# WiFiGeiger.net
KiCad netlist of a schematic drawn in EAGLE
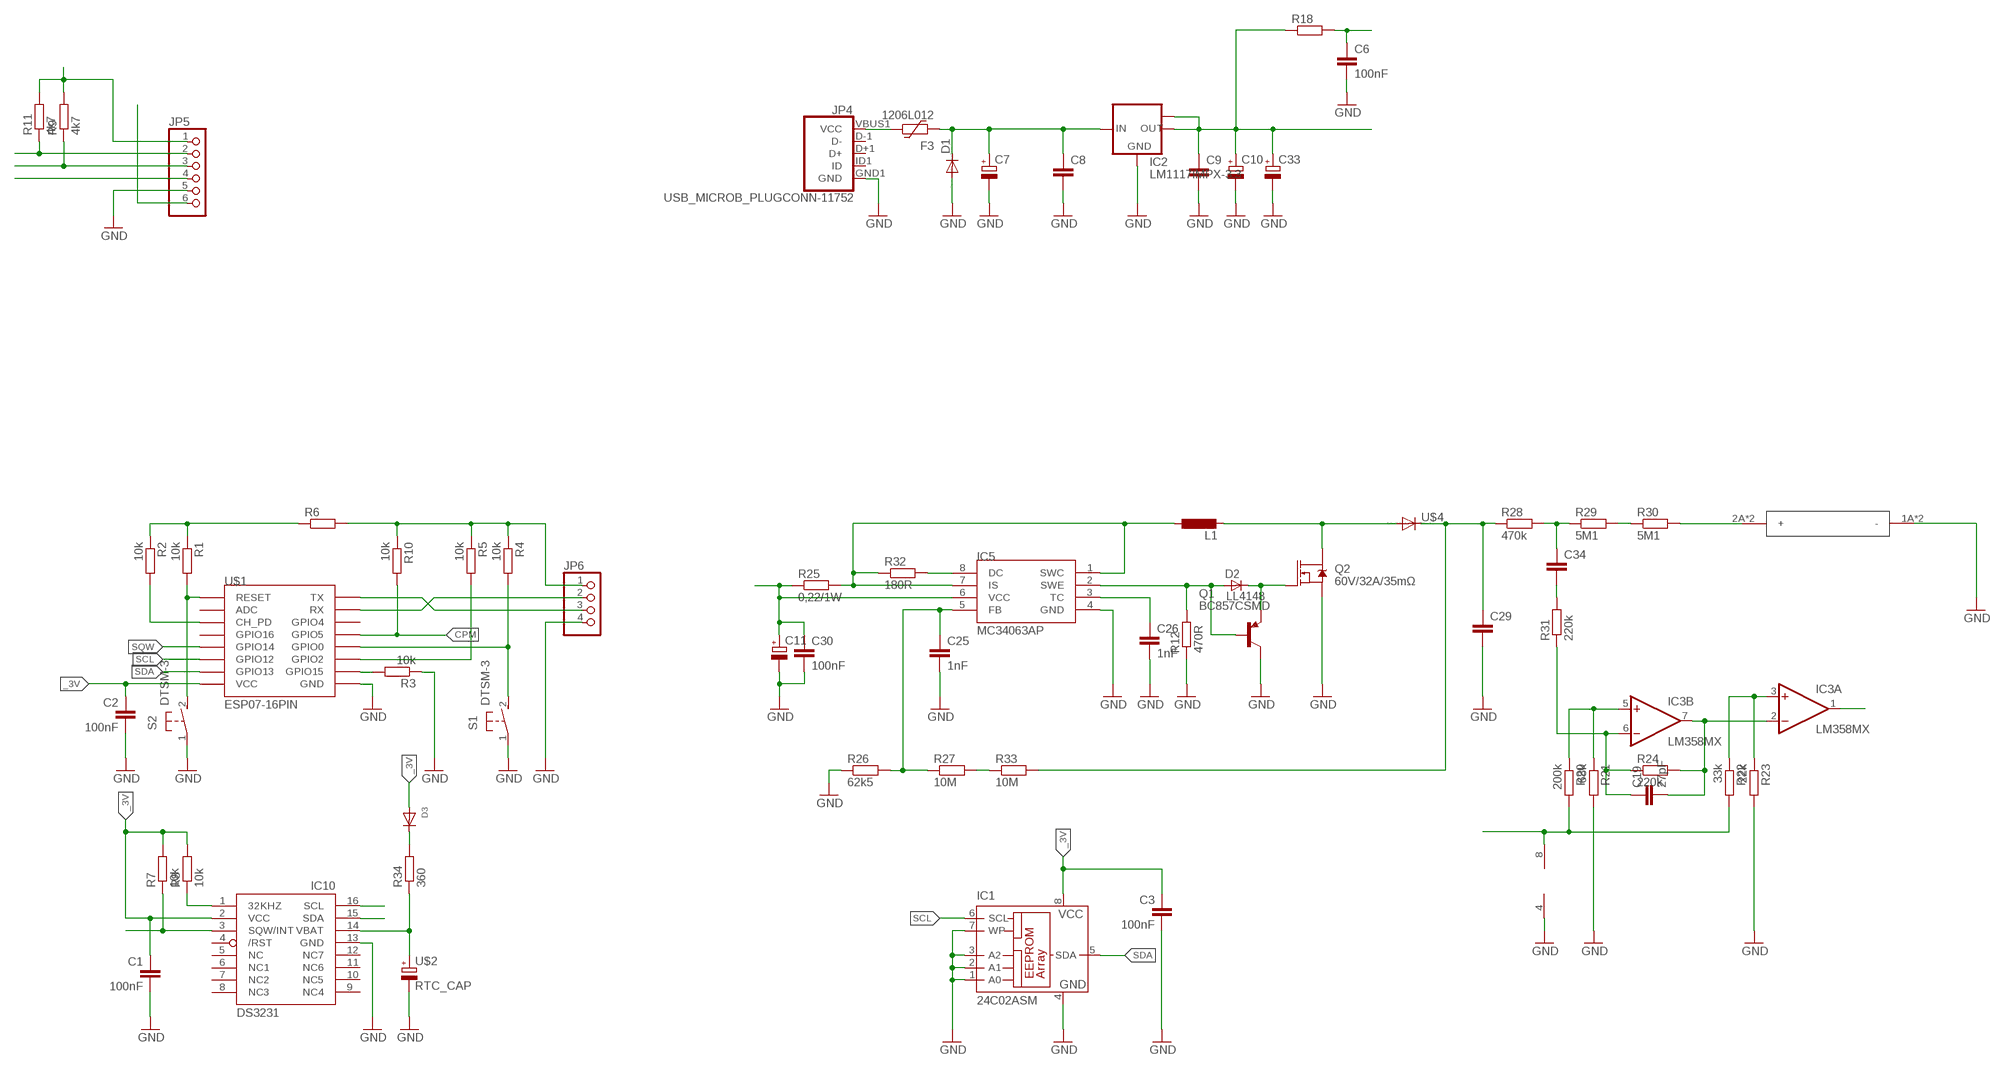
[diagram p0: schematic, sheet 1]

(export (version "E")
  (design (tool "Eeschema 10.0.6"))
  (components
    (comp (ref "C1")
      (value "100nF")
      (footprint "eagle-import:C0603")
      (libsource (lib "eagle-import") (part "C-EUC0603"))
    )
    (comp (ref "C2")
      (value "100nF")
      (footprint "eagle-import:C0603")
      (libsource (lib "eagle-import") (part "C-EUC0603"))
    )
    (comp (ref "C3")
      (value "100nF")
      (footprint "eagle-import:C0603")
      (libsource (lib "eagle-import") (part "C-EUC0603"))
    )
    (comp (ref "C6")
      (value "100nF")
      (footprint "eagle-import:C0603")
      (libsource (lib "eagle-import") (part "C-EUC0603"))
    )
    (comp (ref "C7")
      (value "CPOL-EUSMCC")
      (footprint "eagle-import:SMC_C")
      (libsource (lib "eagle-import") (part "CPOL-EUSMCC"))
    )
    (comp (ref "C8")
      (value "C-EUC1206")
      (footprint "eagle-import:C1206")
      (libsource (lib "eagle-import") (part "C-EUC1206"))
    )
    (comp (ref "C9")
      (value "C-EUC1206")
      (footprint "eagle-import:C1206")
      (libsource (lib "eagle-import") (part "C-EUC1206"))
    )
    (comp (ref "C10")
      (value "CPOL-EUSMCC")
      (footprint "eagle-import:SMC_C")
      (libsource (lib "eagle-import") (part "CPOL-EUSMCC"))
    )
    (comp (ref "C11")
      (value "CPOL-EUSMCE")
      (footprint "eagle-import:SMC_E")
      (libsource (lib "eagle-import") (part "CPOL-EUSMCE"))
    )
    (comp (ref "C19")
      (value "27pF")
      (footprint "eagle-import:C0603")
      (libsource (lib "eagle-import") (part "C-EUC0603"))
    )
    (comp (ref "C25")
      (value "1nF")
      (footprint "eagle-import:C0603")
      (libsource (lib "eagle-import") (part "C-EUC0603"))
    )
    (comp (ref "C26")
      (value "1nF")
      (footprint "eagle-import:C0603")
      (libsource (lib "eagle-import") (part "C-EUC0603"))
    )
    (comp (ref "C29")
      (value "C-EU225-113X268")
      (footprint "eagle-import:C225-113X268")
      (libsource (lib "eagle-import") (part "C-EU225-113X268"))
    )
    (comp (ref "C30")
      (value "100nF")
      (footprint "eagle-import:C0603")
      (libsource (lib "eagle-import") (part "C-EUC0603"))
    )
    (comp (ref "C33")
      (value "CPOL-EUSMCB")
      (footprint "eagle-import:SMC_B")
      (libsource (lib "eagle-import") (part "CPOL-EUSMCB"))
    )
    (comp (ref "C34")
      (value "C-EU050-024X044")
      (footprint "eagle-import:C050-024X044")
      (libsource (lib "eagle-import") (part "C-EU050-024X044"))
    )
    (comp (ref "D1")
      (value "DIODE-SMB")
      (footprint "eagle-import:SMB")
      (libsource (lib "eagle-import") (part "DIODE-SMB"))
    )
    (comp (ref "D2")
      (value "LL4148")
      (footprint "eagle-import:SOD80_DO213AA_MINIMELF")
      (libsource (lib "eagle-import") (part "LL4148"))
    )
    (comp (ref "D3")
      (value "DIODESMA")
      (footprint "eagle-import:SMADIODE")
      (libsource (lib "eagle-import") (part "DIODESMA"))
    )
    (comp (ref "F3")
      (value "1206L012")
      (footprint "eagle-import:1206L")
      (fields (field (name "MF") "Littelfuse"))
      (libsource (lib "eagle-import") (part "?1206L012"))
    )
    (comp (ref "IC1")
      (value "24C02ASM")
      (footprint "eagle-import:SO-08M")
      (fields (field (name "MF") "MICROCHIP") (field (name "MPN") "24C02C/SN"))
      (libsource (lib "eagle-import") (part "24SMC02A"))
    )
    (comp (ref "IC2")
      (value "LM1117IMPX-3.3")
      (footprint "eagle-import:SOT223")
      (libsource (lib "eagle-import") (part "LM1117IMPX-3.3"))
    )
    (comp (ref "IC3")
      (value "LM358MX")
      (footprint "eagle-import:SO08")
      (libsource (lib "eagle-import") (part "LM358MX"))
    )
    (comp (ref "IC5")
      (value "MC34063AP")
      (footprint "eagle-import:DIL08")
      (libsource (lib "eagle-import") (part "MC34063AP"))
    )
    (comp (ref "IC10")
      (value "DS3231/SO")
      (footprint "eagle-import:SO16W")
      (libsource (lib "eagle-import") (part "DS3231/SO"))
    )
    (comp (ref "JP4")
      (value "USB_MICROB_PLUGCONN-11752")
      (footprint "eagle-import:USB-B-MICRO-SMD_V03")
      (libsource (lib "eagle-import") (part "USB_MICROB_PLUGCONN-11752"))
    )
    (comp (ref "JP5")
      (value "PINHD-1X6")
      (footprint "eagle-import:1X06")
      (libsource (lib "eagle-import") (part "PINHD-1X6"))
    )
    (comp (ref "JP6")
      (value "PINHD-1X4")
      (footprint "eagle-import:1X04")
      (libsource (lib "eagle-import") (part "PINHD-1X4"))
    )
    (comp (ref "L1")
      (value "L-EU6000-XXX-RC")
      (footprint "eagle-import:6000-XXXX-RC")
      (libsource (lib "eagle-import") (part "L-EU6000-XXX-RC"))
    )
    (comp (ref "Q1")
      (value "BC857CSMD")
      (footprint "eagle-import:SOT23-BEC")
      (libsource (lib "eagle-import") (part "BC857SMDC"))
    )
    (comp (ref "Q2")
      (value "60V/32A/35mΩ")
      (footprint "eagle-import:TO220V")
      (libsource (lib "eagle-import") (part "MOSFET-NCH-FQP30N06L"))
    )
    (comp (ref "R1")
      (value "10k")
      (footprint "eagle-import:R0603")
      (libsource (lib "eagle-import") (part "R-EU_R0603"))
    )
    (comp (ref "R2")
      (value "10k")
      (footprint "eagle-import:R0603")
      (libsource (lib "eagle-import") (part "R-EU_R0603"))
    )
    (comp (ref "R3")
      (value "10k")
      (footprint "eagle-import:R0603")
      (libsource (lib "eagle-import") (part "R-EU_R0603"))
    )
    (comp (ref "R4")
      (value "10k")
      (footprint "eagle-import:R0603")
      (libsource (lib "eagle-import") (part "R-EU_R0603"))
    )
    (comp (ref "R5")
      (value "10k")
      (footprint "eagle-import:R0603")
      (libsource (lib "eagle-import") (part "R-EU_R0603"))
    )
    (comp (ref "R6")
      (value "R-EU_R2010")
      (footprint "eagle-import:R2010")
      (libsource (lib "eagle-import") (part "R-EU_R2010"))
    )
    (comp (ref "R7")
      (value "10k")
      (footprint "eagle-import:R0603")
      (libsource (lib "eagle-import") (part "R-EU_R0603"))
    )
    (comp (ref "R8")
      (value "10k")
      (footprint "eagle-import:R0603")
      (libsource (lib "eagle-import") (part "R-EU_R0603"))
    )
    (comp (ref "R9")
      (value "4k7")
      (footprint "eagle-import:R0603")
      (libsource (lib "eagle-import") (part "R-EU_R0603"))
    )
    (comp (ref "R10")
      (value "10k")
      (footprint "eagle-import:R0603")
      (libsource (lib "eagle-import") (part "R-EU_R0603"))
    )
    (comp (ref "R11")
      (value "4k7")
      (footprint "eagle-import:R0603")
      (libsource (lib "eagle-import") (part "R-EU_R0603"))
    )
    (comp (ref "R12")
      (value "470R")
      (footprint "eagle-import:R1206")
      (libsource (lib "eagle-import") (part "R-EU_R1206"))
    )
    (comp (ref "R18")
      (value "R-EU_R1206")
      (footprint "eagle-import:R1206")
      (libsource (lib "eagle-import") (part "R-EU_R1206"))
    )
    (comp (ref "R20")
      (value "200k")
      (footprint "eagle-import:R0603")
      (libsource (lib "eagle-import") (part "R-EU_R0603"))
    )
    (comp (ref "R21")
      (value "68k")
      (footprint "eagle-import:R0603")
      (libsource (lib "eagle-import") (part "R-EU_R0603"))
    )
    (comp (ref "R22")
      (value "33k")
      (footprint "eagle-import:R1206")
      (libsource (lib "eagle-import") (part "R-EU_R1206"))
    )
    (comp (ref "R23")
      (value "22k")
      (footprint "eagle-import:R0603")
      (libsource (lib "eagle-import") (part "R-EU_R0603"))
    )
    (comp (ref "R24")
      (value "220k")
      (footprint "eagle-import:R0603")
      (libsource (lib "eagle-import") (part "R-EU_R0603"))
    )
    (comp (ref "R25")
      (value "0,22/1W")
      (footprint "eagle-import:R2010")
      (libsource (lib "eagle-import") (part "R-EU_R2010"))
    )
    (comp (ref "R26")
      (value "62k5")
      (footprint "eagle-import:R1206")
      (libsource (lib "eagle-import") (part "R-EU_R1206"))
    )
    (comp (ref "R27")
      (value "10M")
      (footprint "eagle-import:R2512")
      (libsource (lib "eagle-import") (part "R-EU_R2512"))
    )
    (comp (ref "R28")
      (value "470k")
      (footprint "eagle-import:R2512")
      (libsource (lib "eagle-import") (part "R-EU_R2512"))
    )
    (comp (ref "R29")
      (value "5M1")
      (footprint "eagle-import:R2512")
      (libsource (lib "eagle-import") (part "R-EU_R2512"))
    )
    (comp (ref "R30")
      (value "5M1")
      (footprint "eagle-import:R2512")
      (libsource (lib "eagle-import") (part "R-EU_R2512"))
    )
    (comp (ref "R31")
      (value "220k")
      (footprint "eagle-import:R0805")
      (libsource (lib "eagle-import") (part "R-EU_R0805"))
    )
    (comp (ref "R32")
      (value "180R")
      (footprint "eagle-import:R0805")
      (libsource (lib "eagle-import") (part "R-EU_R0805"))
    )
    (comp (ref "R33")
      (value "10M")
      (footprint "eagle-import:R2512")
      (libsource (lib "eagle-import") (part "R-EU_R2512"))
    )
    (comp (ref "R34")
      (value "360")
      (footprint "eagle-import:R0603")
      (libsource (lib "eagle-import") (part "R-EU_R0603"))
    )
    (comp (ref "S1")
      (value "DTSM-3")
      (footprint "eagle-import:DTSM-3")
      (libsource (lib "eagle-import") (part "DTSM-3"))
    )
    (comp (ref "S2")
      (value "DTSM-3")
      (footprint "eagle-import:DTSM-3")
      (libsource (lib "eagle-import") (part "DTSM-3"))
    )
    (comp (ref "U$1")
      (value "ESP07-16PIN")
      (footprint "eagle-import:ESP07-16PIN")
      (libsource (lib "eagle-import") (part "ESP07-16PIN"))
    )
    (comp (ref "U$2")
      (value "RTC_CAP")
      (footprint "eagle-import:RTC_CAP")
      (libsource (lib "eagle-import") (part "RTC_CAP"))
    )
    (comp (ref "U$4")
      (value "DIODE-MELF-MLL41")
      (footprint "eagle-import:MELF-MLL41")
      (libsource (lib "eagle-import") (part "DIODE-MELF-MLL41"))
    )
    (comp (ref "U$5")
      (value "STS5")
      (footprint "eagle-import:GEIGERTUBE")
      (libsource (lib "eagle-import") (part "STS5"))
    )
  )
  (nets
    (net (code "1") (name "/A_3V") (class "Default")
      (node (ref "C6") (pin "1") (pinfunction "1_1") (pintype "passive"))
      (node (ref "IC3") (pin "8") (pinfunction "V+_8") (pintype "power_in"))
      (node (ref "R18") (pin "2") (pinfunction "2_2") (pintype "passive"))
      (node (ref "R20") (pin "2") (pinfunction "2_2") (pintype "passive"))
      (node (ref "R22") (pin "2") (pinfunction "2_2") (pintype "passive"))
    )
    (net (code "2") (name "/VBUS") (class "Default")
      (node (ref "C11") (pin "+") (pinfunction "+_+") (pintype "passive"))
      (node (ref "C30") (pin "1") (pinfunction "1_1") (pintype "passive"))
      (node (ref "C7") (pin "+") (pinfunction "+_+") (pintype "passive"))
      (node (ref "C8") (pin "1") (pinfunction "1_1") (pintype "passive"))
      (node (ref "D1") (pin "C") (pinfunction "C_C") (pintype "passive"))
      (node (ref "F3") (pin "2") (pinfunction "2_2") (pintype "passive"))
      (node (ref "IC2") (pin "3") (pinfunction "IN_3") (pintype "input"))
      (node (ref "IC5") (pin "6") (pinfunction "VCC_6") (pintype "passive"))
      (node (ref "JP5") (pin "6") (pinfunction "6_6") (pintype "passive"))
      (node (ref "R25") (pin "1") (pinfunction "1_1") (pintype "passive"))
    )
    (net (code "3") (name "CPM") (class "Default")
      (node (ref "IC3") (pin "1") (pinfunction "OUT_1") (pintype "output"))
      (node (ref "R10") (pin "2") (pinfunction "2_2") (pintype "passive"))
      (node (ref "U$1") (pin "GPIO5") (pinfunction "GPIO5_GPIO5") (pintype "bidirectional"))
    )
    (net (code "4") (name "GND") (class "Default")
      (node (ref "C1") (pin "2") (pinfunction "2_2") (pintype "passive"))
      (node (ref "C10") (pin "-") (pinfunction "-_-") (pintype "passive"))
      (node (ref "C11") (pin "-") (pinfunction "-_-") (pintype "passive"))
      (node (ref "C2") (pin "2") (pinfunction "2_2") (pintype "passive"))
      (node (ref "C25") (pin "2") (pinfunction "2_2") (pintype "passive"))
      (node (ref "C26") (pin "2") (pinfunction "2_2") (pintype "passive"))
      (node (ref "C29") (pin "2") (pinfunction "2_2") (pintype "passive"))
      (node (ref "C3") (pin "2") (pinfunction "2_2") (pintype "passive"))
      (node (ref "C30") (pin "2") (pinfunction "2_2") (pintype "passive"))
      (node (ref "C33") (pin "-") (pinfunction "-_-") (pintype "passive"))
      (node (ref "C6") (pin "2") (pinfunction "2_2") (pintype "passive"))
      (node (ref "C7") (pin "-") (pinfunction "-_-") (pintype "passive"))
      (node (ref "C8") (pin "2") (pinfunction "2_2") (pintype "passive"))
      (node (ref "C9") (pin "2") (pinfunction "2_2") (pintype "passive"))
      (node (ref "D1") (pin "A") (pinfunction "A_A") (pintype "passive"))
      (node (ref "IC1") (pin "1") (pinfunction "A0_1") (pintype "input"))
      (node (ref "IC1") (pin "2") (pinfunction "A1_2") (pintype "input"))
      (node (ref "IC1") (pin "3") (pinfunction "A2_3") (pintype "input"))
      (node (ref "IC1") (pin "4") (pinfunction "GND_4") (pintype "power_in"))
      (node (ref "IC1") (pin "7") (pinfunction "WP_7") (pintype "input"))
      (node (ref "IC10") (pin "13") (pinfunction "GND_13") (pintype "power_in"))
      (node (ref "IC2") (pin "1") (pinfunction "GND_1") (pintype "input"))
      (node (ref "IC3") (pin "4") (pinfunction "V-_4") (pintype "power_in"))
      (node (ref "IC5") (pin "4") (pinfunction "GND_4") (pintype "passive"))
      (node (ref "JP4") (pin "GND1") (pinfunction "GND_GND1") (pintype "bidirectional"))
      (node (ref "JP5") (pin "5") (pinfunction "5_5") (pintype "passive"))
      (node (ref "JP6") (pin "4") (pinfunction "4_4") (pintype "passive"))
      (node (ref "Q1") (pin "C") (pinfunction "C_C") (pintype "passive"))
      (node (ref "Q2") (pin "3") (pinfunction "S_3") (pintype "bidirectional"))
      (node (ref "R12") (pin "1") (pinfunction "1_1") (pintype "passive"))
      (node (ref "R21") (pin "2") (pinfunction "2_2") (pintype "passive"))
      (node (ref "R23") (pin "2") (pinfunction "2_2") (pintype "passive"))
      (node (ref "R26") (pin "1") (pinfunction "1_1") (pintype "passive"))
      (node (ref "R3") (pin "1") (pinfunction "1_1") (pintype "passive"))
      (node (ref "S1") (pin "1") (pinfunction "1_1") (pintype "passive"))
      (node (ref "S2") (pin "1") (pinfunction "1_1") (pintype "passive"))
      (node (ref "U$1") (pin "GND") (pinfunction "GND_GND") (pintype "bidirectional"))
      (node (ref "U$2") (pin "P$2") (pinfunction "-_P$2") (pintype "passive"))
      (node (ref "U$5") (pin "1A") (pinfunction "-_1A") (pintype "bidirectional"))
      (node (ref "U$5") (pin "1B") (pinfunction "-_1B") (pintype "bidirectional"))
    )
    (net (code "5") (name "Net-(C29-Pad1)") (class "Default")
      (node (ref "C29") (pin "1") (pinfunction "1_1") (pintype "passive"))
      (node (ref "R28") (pin "1") (pinfunction "1_1") (pintype "passive"))
      (node (ref "R33") (pin "2") (pinfunction "2_2") (pintype "passive"))
      (node (ref "U$4") (pin "C") (pinfunction "C_C") (pintype "passive"))
    )
    (net (code "6") (name "Net-(C34-Pad1)") (class "Default")
      (node (ref "C34") (pin "1") (pinfunction "1_1") (pintype "passive"))
      (node (ref "R28") (pin "2") (pinfunction "2_2") (pintype "passive"))
      (node (ref "R29") (pin "1") (pinfunction "1_1") (pintype "passive"))
    )
    (net (code "7") (name "Net-(C34-Pad2)") (class "Default")
      (node (ref "C34") (pin "2") (pinfunction "2_2") (pintype "passive"))
      (node (ref "R31") (pin "2") (pinfunction "2_2") (pintype "passive"))
    )
    (net (code "8") (name "Net-(D3-PadC)") (class "Default")
      (node (ref "D3") (pin "C") (pinfunction "C_C") (pintype "passive"))
      (node (ref "R34") (pin "2") (pinfunction "2_2") (pintype "passive"))
    )
    (net (code "9") (name "Net-(IC3A-+IN)") (class "Default")
      (node (ref "IC3") (pin "3") (pinfunction "+IN_3") (pintype "input"))
      (node (ref "R22") (pin "1") (pinfunction "1_1") (pintype "passive"))
      (node (ref "R23") (pin "1") (pinfunction "1_1") (pintype "passive"))
    )
    (net (code "10") (name "Net-(IC3A--IN)") (class "Default")
      (node (ref "C19") (pin "2") (pinfunction "2_2") (pintype "passive"))
      (node (ref "IC3") (pin "2") (pinfunction "-IN_2") (pintype "input"))
      (node (ref "IC3") (pin "7") (pinfunction "OUT_7") (pintype "output"))
      (node (ref "R24") (pin "2") (pinfunction "2_2") (pintype "passive"))
    )
    (net (code "11") (name "Net-(IC3B-+IN)") (class "Default")
      (node (ref "IC3") (pin "5") (pinfunction "+IN_5") (pintype "input"))
      (node (ref "R20") (pin "1") (pinfunction "1_1") (pintype "passive"))
      (node (ref "R21") (pin "1") (pinfunction "1_1") (pintype "passive"))
    )
    (net (code "12") (name "Net-(IC3B--IN)") (class "Default")
      (node (ref "C19") (pin "1") (pinfunction "1_1") (pintype "passive"))
      (node (ref "IC3") (pin "6") (pinfunction "-IN_6") (pintype "input"))
      (node (ref "R24") (pin "1") (pinfunction "1_1") (pintype "passive"))
      (node (ref "R31") (pin "1") (pinfunction "1_1") (pintype "passive"))
    )
    (net (code "13") (name "Net-(IC5-DC)") (class "Default")
      (node (ref "IC5") (pin "8") (pinfunction "DC_8") (pintype "passive"))
      (node (ref "R32") (pin "2") (pinfunction "2_2") (pintype "passive"))
    )
    (net (code "14") (name "Net-(IC5-FB)") (class "Default")
      (node (ref "C25") (pin "1") (pinfunction "1_1") (pintype "passive"))
      (node (ref "IC5") (pin "5") (pinfunction "FB_5") (pintype "passive"))
      (node (ref "R26") (pin "2") (pinfunction "2_2") (pintype "passive"))
      (node (ref "R27") (pin "1") (pinfunction "1_1") (pintype "passive"))
    )
    (net (code "15") (name "Net-(IC5-IS)") (class "Default")
      (node (ref "IC5") (pin "1") (pinfunction "SWC_1") (pintype "passive"))
      (node (ref "IC5") (pin "7") (pinfunction "IS_7") (pintype "passive"))
      (node (ref "L1") (pin "1") (pinfunction "1_1") (pintype "passive"))
      (node (ref "R25") (pin "2") (pinfunction "2_2") (pintype "passive"))
      (node (ref "R32") (pin "1") (pinfunction "1_1") (pintype "passive"))
    )
    (net (code "16") (name "Net-(IC5-SWE)") (class "Default")
      (node (ref "D2") (pin "A") (pinfunction "A_A") (pintype "passive"))
      (node (ref "IC5") (pin "2") (pinfunction "SWE_2") (pintype "passive"))
      (node (ref "Q1") (pin "B") (pinfunction "B_B") (pintype "passive"))
      (node (ref "R12") (pin "2") (pinfunction "2_2") (pintype "passive"))
    )
    (net (code "17") (name "Net-(IC5-TC)") (class "Default")
      (node (ref "C26") (pin "1") (pinfunction "1_1") (pintype "passive"))
      (node (ref "IC5") (pin "3") (pinfunction "TC_3") (pintype "passive"))
    )
    (net (code "18") (name "Net-(IC10-32KHZ)") (class "Default")
      (node (ref "IC10") (pin "1") (pinfunction "32KHZ_1") (pintype "output"))
      (node (ref "R8") (pin "1") (pinfunction "1_1") (pintype "passive"))
    )
    (net (code "19") (name "Net-(IC10-VBAT)") (class "Default")
      (node (ref "IC10") (pin "14") (pinfunction "VBAT_14") (pintype "power_in"))
      (node (ref "R34") (pin "1") (pinfunction "1_1") (pintype "passive"))
      (node (ref "U$2") (pin "P$1") (pinfunction "+_P$1") (pintype "passive"))
    )
    (net (code "20") (name "Net-(JP4-VCC)") (class "Default")
      (node (ref "F3") (pin "1") (pinfunction "1_1") (pintype "passive"))
      (node (ref "JP4") (pin "VBUS1") (pinfunction "VCC_VBUS1") (pintype "bidirectional"))
    )
    (net (code "21") (name "Net-(JP6-Pad1)") (class "Default")
      (node (ref "JP6") (pin "1") (pinfunction "1_1") (pintype "passive"))
      (node (ref "R10") (pin "1") (pinfunction "1_1") (pintype "passive"))
      (node (ref "R4") (pin "1") (pinfunction "1_1") (pintype "passive"))
      (node (ref "R5") (pin "1") (pinfunction "1_1") (pintype "passive"))
      (node (ref "R6") (pin "2") (pinfunction "2_2") (pintype "passive"))
    )
    (net (code "22") (name "Net-(JP6-Pad2)") (class "Default")
      (node (ref "JP6") (pin "2") (pinfunction "2_2") (pintype "passive"))
      (node (ref "U$1") (pin "RX") (pinfunction "RX_RX") (pintype "bidirectional"))
    )
    (net (code "23") (name "Net-(JP6-Pad3)") (class "Default")
      (node (ref "JP6") (pin "3") (pinfunction "3_3") (pintype "passive"))
      (node (ref "U$1") (pin "TX") (pinfunction "TX_TX") (pintype "bidirectional"))
    )
    (net (code "24") (name "Net-(Q2-D)") (class "Default")
      (node (ref "L1") (pin "2") (pinfunction "2_2") (pintype "passive"))
      (node (ref "Q2") (pin "2") (pinfunction "D_2") (pintype "bidirectional"))
      (node (ref "U$4") (pin "A") (pinfunction "A_A") (pintype "passive"))
    )
    (net (code "25") (name "Net-(Q2-G)") (class "Default")
      (node (ref "D2") (pin "C") (pinfunction "C_C") (pintype "passive"))
      (node (ref "Q1") (pin "E") (pinfunction "E_E") (pintype "passive"))
      (node (ref "Q2") (pin "1") (pinfunction "G_1") (pintype "bidirectional"))
    )
    (net (code "26") (name "Net-(R2-Pad2)") (class "Default")
      (node (ref "R2") (pin "2") (pinfunction "2_2") (pintype "passive"))
      (node (ref "U$1") (pin "CH_PD") (pinfunction "CH_PD_CH_PD") (pintype "bidirectional"))
    )
    (net (code "27") (name "Net-(R3-Pad2)") (class "Default")
      (node (ref "R3") (pin "2") (pinfunction "2_2") (pintype "passive"))
      (node (ref "U$1") (pin "GPIO15") (pinfunction "GPIO15_GPIO15") (pintype "bidirectional"))
    )
    (net (code "28") (name "Net-(R4-Pad2)") (class "Default")
      (node (ref "R4") (pin "2") (pinfunction "2_2") (pintype "passive"))
      (node (ref "S1") (pin "2") (pinfunction "2_2") (pintype "passive"))
      (node (ref "U$1") (pin "GPIO0") (pinfunction "GPIO0_GPIO0") (pintype "bidirectional"))
    )
    (net (code "29") (name "Net-(R5-Pad2)") (class "Default")
      (node (ref "R5") (pin "2") (pinfunction "2_2") (pintype "passive"))
      (node (ref "U$1") (pin "GPIO2") (pinfunction "GPIO2_GPIO2") (pintype "bidirectional"))
    )
    (net (code "30") (name "Net-(R27-Pad2)") (class "Default")
      (node (ref "R27") (pin "2") (pinfunction "2_2") (pintype "passive"))
      (node (ref "R33") (pin "1") (pinfunction "1_1") (pintype "passive"))
    )
    (net (code "31") (name "Net-(R29-Pad2)") (class "Default")
      (node (ref "R29") (pin "2") (pinfunction "2_2") (pintype "passive"))
      (node (ref "R30") (pin "1") (pinfunction "1_1") (pintype "passive"))
    )
    (net (code "32") (name "Net-(R30-Pad2)") (class "Default")
      (node (ref "R30") (pin "2") (pinfunction "2_2") (pintype "passive"))
      (node (ref "U$5") (pin "2A") (pinfunction "+_2A") (pintype "bidirectional"))
      (node (ref "U$5") (pin "2B") (pinfunction "+_2B") (pintype "bidirectional"))
    )
    (net (code "33") (name "Net-(U$1-RESET)") (class "Default")
      (node (ref "R1") (pin "2") (pinfunction "2_2") (pintype "passive"))
      (node (ref "S2") (pin "2") (pinfunction "2_2") (pintype "passive"))
      (node (ref "U$1") (pin "REST") (pinfunction "RESET_REST") (pintype "bidirectional"))
    )
    (net (code "34") (name "SCL") (class "Default")
      (node (ref "IC1") (pin "6") (pinfunction "SCL_6") (pintype "input"))
      (node (ref "IC10") (pin "16") (pinfunction "SCL_16") (pintype "bidirectional"))
      (node (ref "JP5") (pin "3") (pinfunction "3_3") (pintype "passive"))
      (node (ref "R9") (pin "1") (pinfunction "1_1") (pintype "passive"))
      (node (ref "U$1") (pin "GPIO12") (pinfunction "GPIO12_GPIO12") (pintype "bidirectional"))
    )
    (net (code "35") (name "SDA") (class "Default")
      (node (ref "IC1") (pin "5") (pinfunction "SDA_5") (pintype "bidirectional"))
      (node (ref "IC10") (pin "15") (pinfunction "SDA_15") (pintype "bidirectional"))
      (node (ref "JP5") (pin "2") (pinfunction "2_2") (pintype "passive"))
      (node (ref "R11") (pin "1") (pinfunction "1_1") (pintype "passive"))
      (node (ref "U$1") (pin "GPIO13") (pinfunction "GPIO13_GPIO13") (pintype "bidirectional"))
    )
    (net (code "36") (name "SQW") (class "Default")
      (node (ref "IC10") (pin "3") (pinfunction "SQW/INT_3") (pintype "output"))
      (node (ref "R7") (pin "1") (pinfunction "1_1") (pintype "passive"))
      (node (ref "U$1") (pin "GPIO14") (pinfunction "GPIO14_GPIO14") (pintype "bidirectional"))
    )
    (net (code "37") (name "_3V") (class "Default")
      (node (ref "C1") (pin "1") (pinfunction "1_1") (pintype "passive"))
      (node (ref "C10") (pin "+") (pinfunction "+_+") (pintype "passive"))
      (node (ref "C2") (pin "1") (pinfunction "1_1") (pintype "passive"))
      (node (ref "C3") (pin "1") (pinfunction "1_1") (pintype "passive"))
      (node (ref "C33") (pin "+") (pinfunction "+_+") (pintype "passive"))
      (node (ref "C9") (pin "1") (pinfunction "1_1") (pintype "passive"))
      (node (ref "D3") (pin "A") (pinfunction "A_A") (pintype "passive"))
      (node (ref "IC1") (pin "8") (pinfunction "VCC_8") (pintype "power_in"))
      (node (ref "IC10") (pin "2") (pinfunction "VCC_2") (pintype "power_in"))
      (node (ref "IC2") (pin "2") (pinfunction "OUT_2") (pintype "passive"))
      (node (ref "IC2") (pin "TAB") (pinfunction "OUT1_TAB") (pintype "passive"))
      (node (ref "JP5") (pin "1") (pinfunction "1_1") (pintype "passive"))
      (node (ref "R1") (pin "1") (pinfunction "1_1") (pintype "passive"))
      (node (ref "R11") (pin "2") (pinfunction "2_2") (pintype "passive"))
      (node (ref "R18") (pin "1") (pinfunction "1_1") (pintype "passive"))
      (node (ref "R2") (pin "1") (pinfunction "1_1") (pintype "passive"))
      (node (ref "R6") (pin "1") (pinfunction "1_1") (pintype "passive"))
      (node (ref "R7") (pin "2") (pinfunction "2_2") (pintype "passive"))
      (node (ref "R8") (pin "2") (pinfunction "2_2") (pintype "passive"))
      (node (ref "R9") (pin "2") (pinfunction "2_2") (pintype "passive"))
      (node (ref "U$1") (pin "VCC") (pinfunction "VCC_VCC") (pintype "bidirectional"))
    )
    (net (code "38") (name "unconnected-(IC10-NC-Pad5)") (class "Default")
      (node (ref "IC10") (pin "5") (pinfunction "NC_5") (pintype "no_connect"))
    )
    (net (code "39") (name "unconnected-(IC10-NC1-Pad6)") (class "Default")
      (node (ref "IC10") (pin "6") (pinfunction "NC1_6") (pintype "no_connect"))
    )
    (net (code "40") (name "unconnected-(IC10-NC2-Pad7)") (class "Default")
      (node (ref "IC10") (pin "7") (pinfunction "NC2_7") (pintype "no_connect"))
    )
    (net (code "41") (name "unconnected-(IC10-NC3-Pad8)") (class "Default")
      (node (ref "IC10") (pin "8") (pinfunction "NC3_8") (pintype "no_connect"))
    )
    (net (code "42") (name "unconnected-(IC10-NC4-Pad9)") (class "Default")
      (node (ref "IC10") (pin "9") (pinfunction "NC4_9") (pintype "no_connect"))
    )
    (net (code "43") (name "unconnected-(IC10-NC5-Pad10)") (class "Default")
      (node (ref "IC10") (pin "10") (pinfunction "NC5_10") (pintype "no_connect"))
    )
    (net (code "44") (name "unconnected-(IC10-NC6-Pad11)") (class "Default")
      (node (ref "IC10") (pin "11") (pinfunction "NC6_11") (pintype "no_connect"))
    )
    (net (code "45") (name "unconnected-(IC10-NC7-Pad12)") (class "Default")
      (node (ref "IC10") (pin "12") (pinfunction "NC7_12") (pintype "no_connect"))
    )
    (net (code "46") (name "unconnected-(IC10-{slash}RST-Pad4)") (class "Default")
      (node (ref "IC10") (pin "4") (pinfunction "/RST_4") (pintype "passive"))
    )
    (net (code "47") (name "unconnected-(JP4-D+-PadD+1)") (class "Default")
      (node (ref "JP4") (pin "D+1") (pinfunction "D+_D+1") (pintype "bidirectional"))
    )
    (net (code "48") (name "unconnected-(JP4-D--PadD-1)") (class "Default")
      (node (ref "JP4") (pin "D-1") (pinfunction "D-_D-1") (pintype "bidirectional"))
    )
    (net (code "49") (name "unconnected-(JP4-ID-PadID1)") (class "Default")
      (node (ref "JP4") (pin "ID1") (pinfunction "ID_ID1") (pintype "bidirectional"))
    )
    (net (code "50") (name "unconnected-(JP5-Pad4)") (class "Default")
      (node (ref "JP5") (pin "4") (pinfunction "4_4") (pintype "passive"))
    )
    (net (code "51") (name "unconnected-(U$1-PadADC)") (class "Default")
      (node (ref "U$1") (pin "ADC") (pinfunction "ADC_ADC") (pintype "bidirectional"))
    )
    (net (code "52") (name "unconnected-(U$1-PadGPIO4)") (class "Default")
      (node (ref "U$1") (pin "GPIO4") (pinfunction "GPIO4_GPIO4") (pintype "bidirectional"))
    )
    (net (code "53") (name "unconnected-(U$1-PadGPIO16)") (class "Default")
      (node (ref "U$1") (pin "GPIO16") (pinfunction "GPIO16_GPIO16") (pintype "bidirectional"))
    )
  )
)
